# 03_ICs.net
KiCad netlist of a schematic drawn in Altium Designer
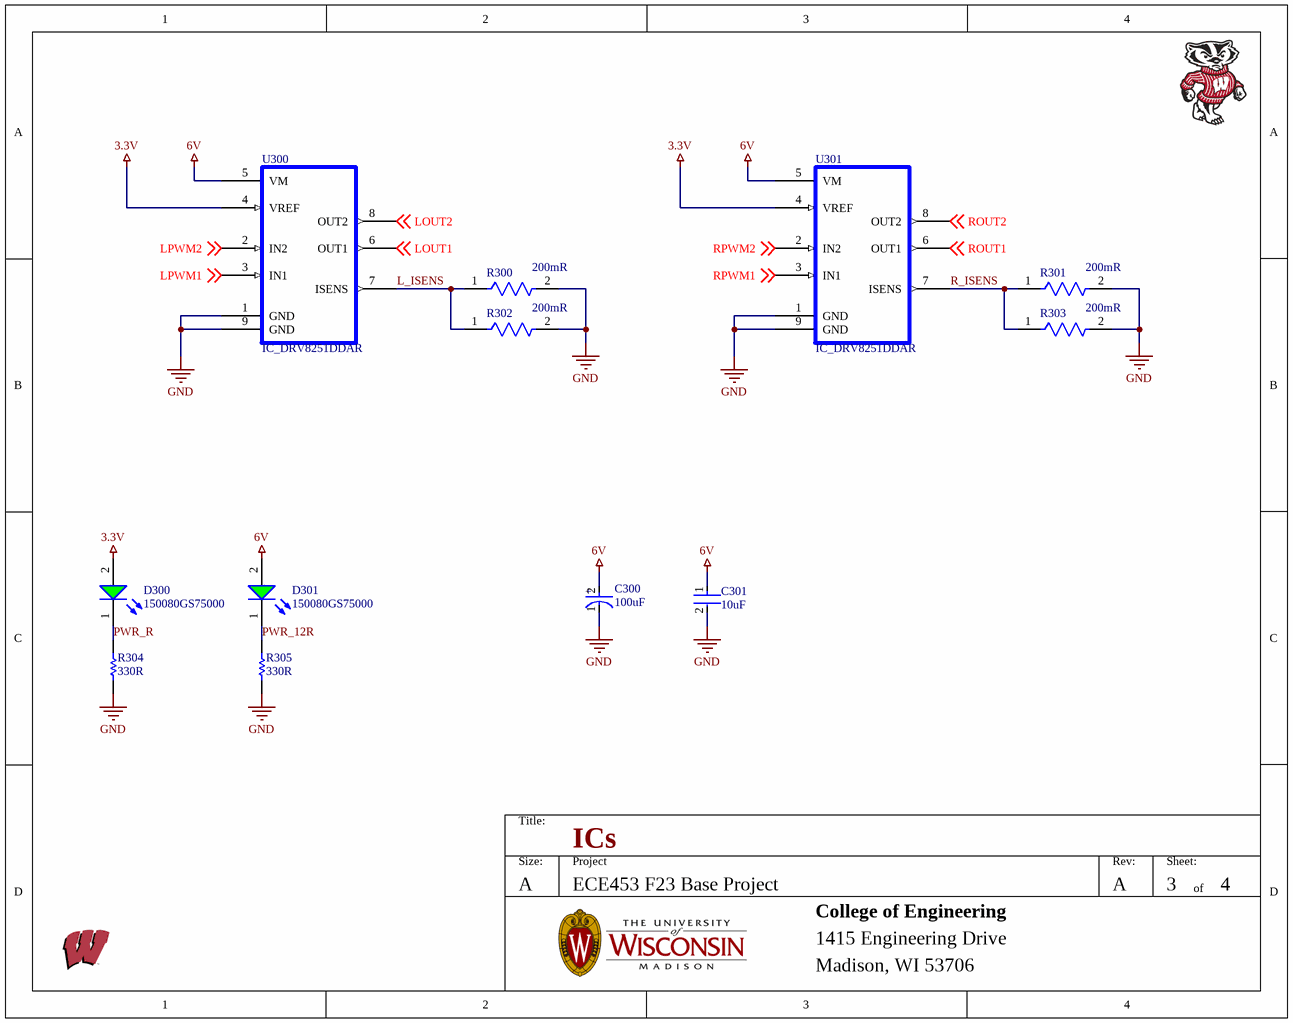
[diagram p0: 03_ICs.SchDoc]

(export (version "E")
  (design (tool "Eeschema 10.0.6"))
  (components
    (comp (ref "C300")
      (value "100uF")
      (footprint "FP-SD8-MFG")
      (description "CAP ALUM 100UF 20% 25V SMD")
      (fields (field (name "VOLTAGE") "25V") (field (name "TOLERANCE") "20%"))
      (libsource (lib "Altium Content Vault") (part "a00bbbee19879c290e62620ae7e47b1"))
    )
    (comp (ref "C301")
      (value "10uF")
      (footprint "FP-C0805C-DG-MFG")
      (description "CAP CER 10UF 10V X5R 0805")
      (fields (field (name "TOLERANCE") "10%") (field (name "MANUFACTURER PART NUMBER") "C0805C106K8PACTU"))
      (libsource (lib "Altium Content Vault") (part "11868f565c42a9108669ba33697ecf6"))
    )
    (comp (ref "D300")
      (value "150080GS75000")
      (footprint "WL-SMCW_0805_150080xx75000")
      (libsource (lib "Altium Content Vault") (part "LED_Green_2A-1K"))
    )
    (comp (ref "D301")
      (value "150080GS75000")
      (footprint "WL-SMCW_0805_150080xx75000")
      (libsource (lib "Altium Content Vault") (part "LED_Green_2A-1K"))
    )
    (comp (ref "R300")
      (value "200mR")
      (footprint "FP-CSR0805-IPC_C")
      (description "General Purpose Thick Film Chip Resistor, 0805, 0.2Ω, 1%, 200ppm/°C, 0.25W")
      (fields (field (name "TOLERANCE") "1%") (field (name "MANUFACTURER") "Stackpole Electronics"))
      (libsource (lib "Altium Content Vault") (part "1029c3af85768c4190bb7ad29bc67b5"))
    )
    (comp (ref "R301")
      (value "200mR")
      (footprint "FP-CSR0805-IPC_C")
      (description "General Purpose Thick Film Chip Resistor, 0805, 0.2Ω, 1%, 200ppm/°C, 0.25W")
      (fields (field (name "TOLERANCE") "1%") (field (name "MANUFACTURER") "Stackpole Electronics"))
      (libsource (lib "Altium Content Vault") (part "1029c3af85768c4190bb7ad29bc67b5"))
    )
    (comp (ref "R302")
      (value "200mR")
      (footprint "FP-CSR0805-IPC_C")
      (description "General Purpose Thick Film Chip Resistor, 0805, 0.2Ω, 1%, 200ppm/°C, 0.25W")
      (fields (field (name "TOLERANCE") "1%") (field (name "MANUFACTURER") "Stackpole Electronics"))
      (libsource (lib "Altium Content Vault") (part "1029c3af85768c4190bb7ad29bc67b5"))
    )
    (comp (ref "R303")
      (value "200mR")
      (footprint "FP-CSR0805-IPC_C")
      (description "General Purpose Thick Film Chip Resistor, 0805, 0.2Ω, 1%, 200ppm/°C, 0.25W")
      (fields (field (name "TOLERANCE") "1%") (field (name "MANUFACTURER") "Stackpole Electronics"))
      (libsource (lib "Altium Content Vault") (part "1029c3af85768c4190bb7ad29bc67b5"))
    )
    (comp (ref "R304")
      (value "330R")
      (footprint "RESC2013X60X40LL20T25")
      (fields
        (field (name "MANUFACTURER") "Panasonic")
        (field (name "PART NUMBER") "ERA6AEB331V")
        (field (name "MANUFACTURER PART NUMBER") "ERA-6AEB331V")
      )
      (libsource (lib "Altium Content Vault") (part "RES"))
    )
    (comp (ref "R305")
      (value "330R")
      (footprint "RESC2013X60X40LL20T25")
      (fields
        (field (name "MANUFACTURER") "Panasonic")
        (field (name "PART NUMBER") "ERA6AEB331V")
        (field (name "MANUFACTURER PART NUMBER") "ERA-6AEB331V")
      )
      (libsource (lib "Altium Content Vault") (part "RES"))
    )
    (comp (ref "U300")
      (value "IC_DRV8251DDAR")
      (footprint "SOIC_8_PP")
      (description "48-V, 3.5-A H bridge motor driver with current regulation and latched OCP 8-SO PowerPAD -40 to 150")
      (fields
        (field (name "MANUFACTURER") "Texas Instruments")
        (field (name "MANUFACTURER PART NUMBER") "DRV8251DDAR")
      )
      (libsource (lib "ECE453_S24") (part "IC_DRV8251DDAR"))
    )
    (comp (ref "U301")
      (value "IC_DRV8251DDAR")
      (footprint "SOIC_8_PP")
      (description "48-V, 3.5-A H bridge motor driver with current regulation and latched OCP 8-SO PowerPAD -40 to 150")
      (fields
        (field (name "MANUFACTURER") "Texas Instruments")
        (field (name "MANUFACTURER PART NUMBER") "DRV8251DDAR")
      )
      (libsource (lib "ECE453_S24") (part "IC_DRV8251DDAR"))
    )
  )
  (nets
    (net (code "1") (name "/L_ISENS") (class "Default")
      (node (ref "R300") (pin "1") (pinfunction "1_1") (pintype "passive"))
      (node (ref "R302") (pin "1") (pinfunction "1_1") (pintype "passive"))
      (node (ref "U300") (pin "7") (pinfunction "ISENS_7") (pintype "output"))
    )
    (net (code "2") (name "/PWR_12R") (class "Default")
      (node (ref "D301") (pin "1") (pinfunction "K_1") (pintype "passive"))
      (node (ref "R305") (pin "1") (pinfunction "1_1") (pintype "passive"))
    )
    (net (code "3") (name "/PWR_R") (class "Default")
      (node (ref "D300") (pin "1") (pinfunction "K_1") (pintype "passive"))
      (node (ref "R304") (pin "1") (pinfunction "1_1") (pintype "passive"))
    )
    (net (code "4") (name "/R_ISENS") (class "Default")
      (node (ref "R301") (pin "1") (pinfunction "1_1") (pintype "passive"))
      (node (ref "R303") (pin "1") (pinfunction "1_1") (pintype "passive"))
      (node (ref "U301") (pin "7") (pinfunction "ISENS_7") (pintype "output"))
    )
    (net (code "5") (name "3.3V") (class "Default")
      (node (ref "D300") (pin "2") (pinfunction "A_2") (pintype "passive"))
      (node (ref "U300") (pin "4") (pinfunction "VREF_4") (pintype "input"))
      (node (ref "U301") (pin "4") (pinfunction "VREF_4") (pintype "input"))
    )
    (net (code "6") (name "6V") (class "Default")
      (node (ref "C300") (pin "2") (pinfunction "A_2") (pintype "passive"))
      (node (ref "C301") (pin "1") (pinfunction "1_1") (pintype "passive"))
      (node (ref "D301") (pin "2") (pinfunction "A_2") (pintype "passive"))
      (node (ref "U300") (pin "5") (pinfunction "VM_5") (pintype "power_in"))
      (node (ref "U301") (pin "5") (pinfunction "VM_5") (pintype "power_in"))
    )
    (net (code "7") (name "GND") (class "Default")
      (node (ref "C300") (pin "1") (pinfunction "C_1") (pintype "passive"))
      (node (ref "C301") (pin "2") (pinfunction "2_2") (pintype "passive"))
      (node (ref "R300") (pin "2") (pinfunction "2_2") (pintype "passive"))
      (node (ref "R301") (pin "2") (pinfunction "2_2") (pintype "passive"))
      (node (ref "R302") (pin "2") (pinfunction "2_2") (pintype "passive"))
      (node (ref "R303") (pin "2") (pinfunction "2_2") (pintype "passive"))
      (node (ref "R304") (pin "2") (pinfunction "2_2") (pintype "passive"))
      (node (ref "R305") (pin "2") (pinfunction "2_2") (pintype "passive"))
      (node (ref "U300") (pin "1") (pinfunction "GND_1") (pintype "power_in"))
      (node (ref "U300") (pin "9") (pinfunction "GND_9") (pintype "power_in"))
      (node (ref "U301") (pin "1") (pinfunction "GND_1") (pintype "power_in"))
      (node (ref "U301") (pin "9") (pinfunction "GND_9") (pintype "power_in"))
    )
    (net (code "8") (name "LOUT1") (class "Default")
      (node (ref "U300") (pin "6") (pinfunction "OUT1_6") (pintype "output"))
    )
    (net (code "9") (name "LOUT2") (class "Default")
      (node (ref "U300") (pin "8") (pinfunction "OUT2_8") (pintype "output"))
    )
    (net (code "10") (name "LPWM1") (class "Default")
      (node (ref "U300") (pin "3") (pinfunction "IN1_3") (pintype "input"))
    )
    (net (code "11") (name "LPWM2") (class "Default")
      (node (ref "U300") (pin "2") (pinfunction "IN2_2") (pintype "input"))
    )
    (net (code "12") (name "ROUT1") (class "Default")
      (node (ref "U301") (pin "6") (pinfunction "OUT1_6") (pintype "output"))
    )
    (net (code "13") (name "ROUT2") (class "Default")
      (node (ref "U301") (pin "8") (pinfunction "OUT2_8") (pintype "output"))
    )
    (net (code "14") (name "RPWM1") (class "Default")
      (node (ref "U301") (pin "3") (pinfunction "IN1_3") (pintype "input"))
    )
    (net (code "15") (name "RPWM2") (class "Default")
      (node (ref "U301") (pin "2") (pinfunction "IN2_2") (pintype "input"))
    )
  )
)
